# Rev_B.net
KiCad netlist of a schematic drawn in EAGLE
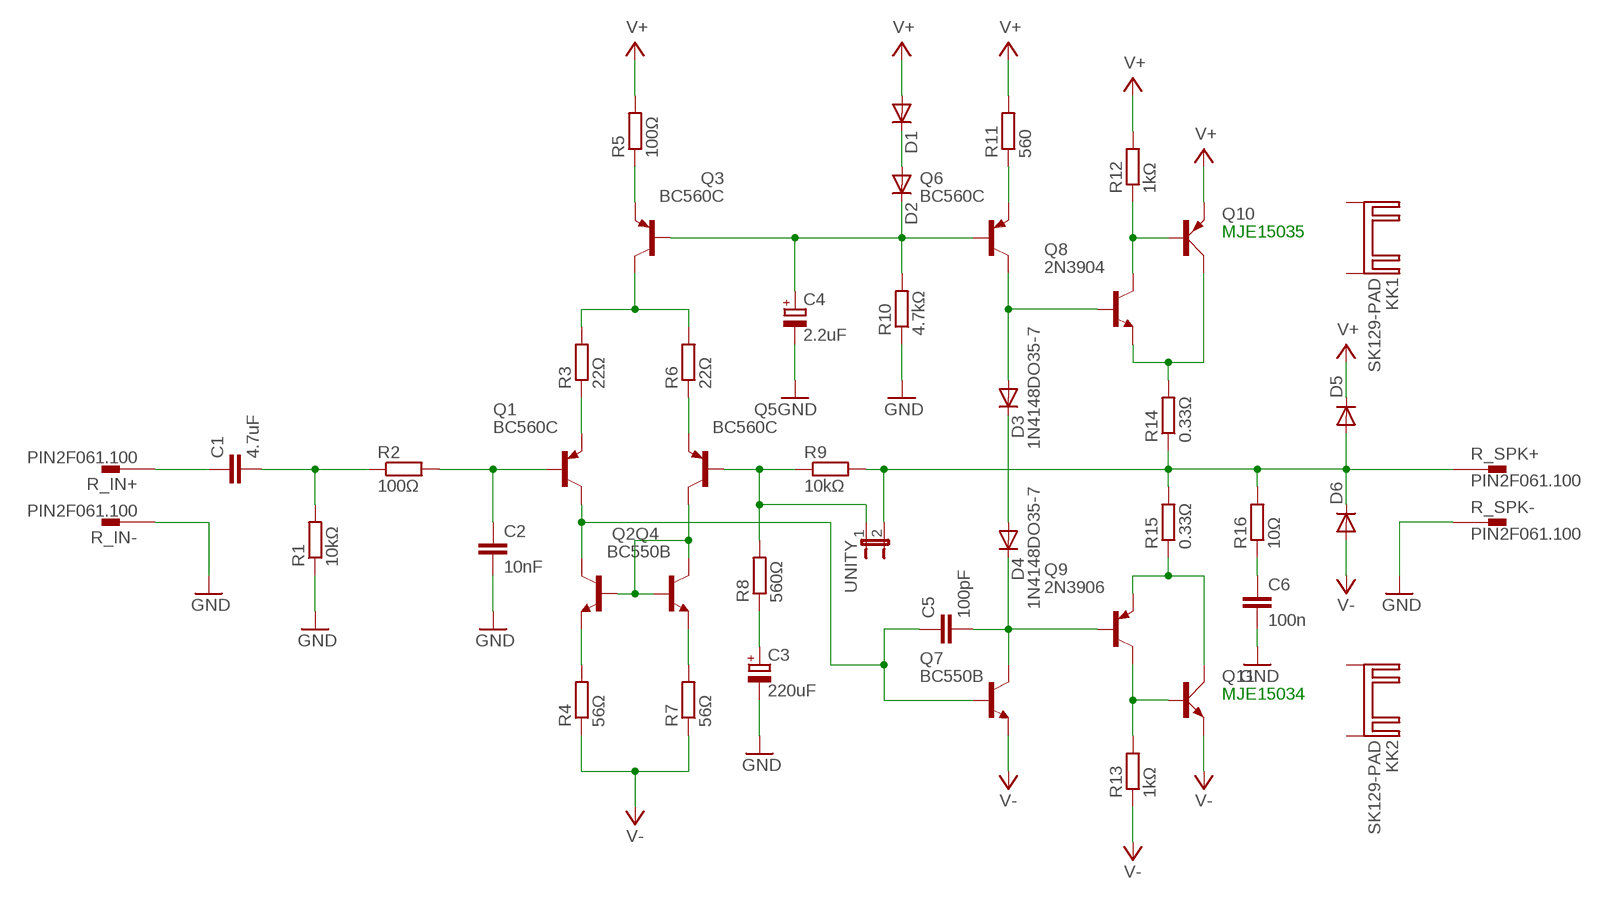
[diagram p0: schematic, sheet 1]
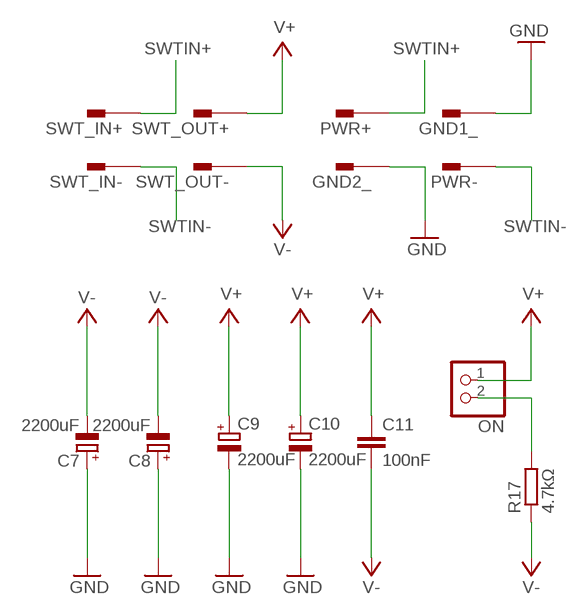
[diagram p1: schematic, sheet 2]

(export (version "E")
  (design (tool "Eeschema 10.0.6"))
  (components
    (comp (ref "C7")
      (value "2200uF")
      (footprint "eagle-import:E5-10,5")
      (libsource (lib "eagle-import") (part "CPOL-EUE5-10.5"))
    )
    (comp (ref "C8")
      (value "2200uF")
      (footprint "eagle-import:E5-10,5")
      (libsource (lib "eagle-import") (part "CPOL-EUE5-10.5"))
    )
    (comp (ref "C9")
      (value "2200uF")
      (footprint "eagle-import:E5-10,5")
      (libsource (lib "eagle-import") (part "CPOL-EUE5-10.5"))
    )
    (comp (ref "C10")
      (value "2200uF")
      (footprint "eagle-import:E5-10,5")
      (libsource (lib "eagle-import") (part "CPOL-EUE5-10.5"))
    )
    (comp (ref "C11")
      (value "100nF")
      (footprint "eagle-import:C025-025X050")
      (libsource (lib "eagle-import") (part "C-EU025-025X050"))
    )
    (comp (ref "GND1_")
      (value "PIN2F061.100")
      (footprint "eagle-import:F061.100")
      (libsource (lib "eagle-import") (part "PIN2F061.100"))
    )
    (comp (ref "GND2_")
      (value "PIN2F061.100")
      (footprint "eagle-import:F061.100")
      (libsource (lib "eagle-import") (part "PIN2F061.100"))
    )
    (comp (ref "ON")
      (value "JST_2PIN-THM")
      (footprint "eagle-import:JST-PH-2-THM")
      (libsource (lib "eagle-import") (part "JST_2PIN-THM"))
    )
    (comp (ref "PWR+")
      (value "PIN2F061.100")
      (footprint "eagle-import:F061.100")
      (libsource (lib "eagle-import") (part "PIN2F061.100"))
    )
    (comp (ref "PWR-")
      (value "PIN2F061.100")
      (footprint "eagle-import:F061.100")
      (libsource (lib "eagle-import") (part "PIN2F061.100"))
    )
    (comp (ref "R17")
      (value "4.7kΩ")
      (footprint "eagle-import:0207_10")
      (libsource (lib "eagle-import") (part "R-EU_0207/10"))
    )
    (comp (ref "SWT_IN+")
      (value "PIN2F061.100")
      (footprint "eagle-import:F061.100")
      (libsource (lib "eagle-import") (part "PIN2F061.100"))
    )
    (comp (ref "SWT_IN-")
      (value "PIN2F061.100")
      (footprint "eagle-import:F061.100")
      (libsource (lib "eagle-import") (part "PIN2F061.100"))
    )
    (comp (ref "SWT_OUT+")
      (value "PIN2F061.100")
      (footprint "eagle-import:F061.100")
      (libsource (lib "eagle-import") (part "PIN2F061.100"))
    )
    (comp (ref "SWT_OUT-")
      (value "PIN2F061.100")
      (footprint "eagle-import:F061.100")
      (libsource (lib "eagle-import") (part "PIN2F061.100"))
    )
    (comp (ref "C1")
      (value "4.7uF")
      (footprint "eagle-import:C225-113X268")
      (libsource (lib "eagle-import") (part "C-EU225-113X268"))
    )
    (comp (ref "C2")
      (value "10nF")
      (footprint "eagle-import:C025-025X050")
      (libsource (lib "eagle-import") (part "C-EU025-025X050"))
    )
    (comp (ref "C3")
      (value "220uF")
      (footprint "eagle-import:E3,5-8")
      (libsource (lib "eagle-import") (part "CPOL-EUE3.5-8"))
    )
    (comp (ref "C4")
      (value "2.2uF")
      (footprint "eagle-import:E2-5")
      (libsource (lib "eagle-import") (part "CPOL-EUE2-5"))
    )
    (comp (ref "C5")
      (value "100pF")
      (footprint "eagle-import:C050-050X075")
      (libsource (lib "eagle-import") (part "C-EU050-050X075"))
    )
    (comp (ref "C6")
      (value "100n")
      (footprint "eagle-import:C075-042X103")
      (libsource (lib "eagle-import") (part "C-EU075-042X103"))
    )
    (comp (ref "D1")
      (value "1N4148DO35-7")
      (footprint "eagle-import:DO35-7")
      (libsource (lib "eagle-import") (part "1N4148DO35-7"))
    )
    (comp (ref "D2")
      (value "1N4148DO35-7")
      (footprint "eagle-import:DO35-7")
      (libsource (lib "eagle-import") (part "1N4148DO35-7"))
    )
    (comp (ref "D3")
      (value "1N4148DO35-7")
      (footprint "eagle-import:DO35-7")
      (libsource (lib "eagle-import") (part "1N4148DO35-7"))
    )
    (comp (ref "D4")
      (value "1N4148DO35-7")
      (footprint "eagle-import:DO35-7")
      (libsource (lib "eagle-import") (part "1N4148DO35-7"))
    )
    (comp (ref "D5")
      (value "1N4148DO35-7")
      (footprint "eagle-import:DO35-7")
      (libsource (lib "eagle-import") (part "1N4148DO35-7"))
    )
    (comp (ref "D6")
      (value "1N4148DO35-7")
      (footprint "eagle-import:DO35-7")
      (libsource (lib "eagle-import") (part "1N4148DO35-7"))
    )
    (comp (ref "KK1")
      (value "SK129-PAD")
      (footprint "eagle-import:SK129")
      (libsource (lib "eagle-import") (part "SK129-PAD"))
    )
    (comp (ref "KK2")
      (value "SK129-PAD")
      (footprint "eagle-import:SK129")
      (libsource (lib "eagle-import") (part "SK129-PAD"))
    )
    (comp (ref "Q1")
      (value "BC560C")
      (footprint "eagle-import:TO92-EBC")
      (libsource (lib "eagle-import") (part "BC560C"))
    )
    (comp (ref "Q2")
      (value "BC550B")
      (footprint "eagle-import:TO92-EBC")
      (libsource (lib "eagle-import") (part "BC550B"))
    )
    (comp (ref "Q3")
      (value "BC560C")
      (footprint "eagle-import:TO92-EBC")
      (libsource (lib "eagle-import") (part "BC560C"))
    )
    (comp (ref "Q4")
      (value "BC550B")
      (footprint "eagle-import:TO92-EBC")
      (libsource (lib "eagle-import") (part "BC550B"))
    )
    (comp (ref "Q5")
      (value "BC560C")
      (footprint "eagle-import:TO92-EBC")
      (libsource (lib "eagle-import") (part "BC560C"))
    )
    (comp (ref "Q6")
      (value "BC560C")
      (footprint "eagle-import:TO92-EBC")
      (libsource (lib "eagle-import") (part "BC560C"))
    )
    (comp (ref "Q7")
      (value "BC550B")
      (footprint "eagle-import:TO92-EBC")
      (libsource (lib "eagle-import") (part "BC550B"))
    )
    (comp (ref "Q8")
      (value "2N3904")
      (footprint "eagle-import:TO92")
      (libsource (lib "eagle-import") (part "2N3904"))
    )
    (comp (ref "Q9")
      (value "2N3906")
      (footprint "eagle-import:TO92")
      (libsource (lib "eagle-import") (part "2N3906"))
    )
    (comp (ref "Q10")
      (value "TIP42C")
      (footprint "eagle-import:TO220AV")
      (libsource (lib "eagle-import") (part "TIP42C"))
    )
    (comp (ref "Q11")
      (value "TIP41C")
      (footprint "eagle-import:TO220AV")
      (libsource (lib "eagle-import") (part "TIP41C"))
    )
    (comp (ref "R1")
      (value "10kΩ")
      (footprint "eagle-import:0207_10")
      (libsource (lib "eagle-import") (part "R-EU_0207/10"))
    )
    (comp (ref "R2")
      (value "100Ω")
      (footprint "eagle-import:0207_10")
      (libsource (lib "eagle-import") (part "R-EU_0207/10"))
    )
    (comp (ref "R3")
      (value "22Ω")
      (footprint "eagle-import:0207_10")
      (libsource (lib "eagle-import") (part "R-EU_0207/10"))
    )
    (comp (ref "R4")
      (value "56Ω")
      (footprint "eagle-import:0207_10")
      (libsource (lib "eagle-import") (part "R-EU_0207/10"))
    )
    (comp (ref "R5")
      (value "100Ω")
      (footprint "eagle-import:0207_10")
      (libsource (lib "eagle-import") (part "R-EU_0207/10"))
    )
    (comp (ref "R6")
      (value "22Ω")
      (footprint "eagle-import:0207_10")
      (libsource (lib "eagle-import") (part "R-EU_0207/10"))
    )
    (comp (ref "R7")
      (value "56Ω")
      (footprint "eagle-import:0207_10")
      (libsource (lib "eagle-import") (part "R-EU_0207/10"))
    )
    (comp (ref "R8")
      (value "560Ω")
      (footprint "eagle-import:0207_10")
      (libsource (lib "eagle-import") (part "R-EU_0207/10"))
    )
    (comp (ref "R9")
      (value "10kΩ")
      (footprint "eagle-import:0207_10")
      (libsource (lib "eagle-import") (part "R-EU_0207/10"))
    )
    (comp (ref "R10")
      (value "4.7kΩ")
      (footprint "eagle-import:0207_10")
      (libsource (lib "eagle-import") (part "R-EU_0207/10"))
    )
    (comp (ref "R11")
      (value "560")
      (footprint "eagle-import:0207_10")
      (libsource (lib "eagle-import") (part "R-EU_0207/10"))
    )
    (comp (ref "R12")
      (value "1kΩ")
      (footprint "eagle-import:0207_10")
      (libsource (lib "eagle-import") (part "R-EU_0207/10"))
    )
    (comp (ref "R13")
      (value "1kΩ")
      (footprint "eagle-import:0207_10")
      (libsource (lib "eagle-import") (part "R-EU_0207/10"))
    )
    (comp (ref "R14")
      (value "0.33Ω")
      (footprint "eagle-import:0309_12")
      (libsource (lib "eagle-import") (part "R-EU_0309/12"))
    )
    (comp (ref "R15")
      (value "0.33Ω")
      (footprint "eagle-import:0309_12")
      (libsource (lib "eagle-import") (part "R-EU_0309/12"))
    )
    (comp (ref "R16")
      (value "10Ω")
      (footprint "eagle-import:0617V")
      (libsource (lib "eagle-import") (part "R-EU_0617/5V"))
    )
    (comp (ref "R_IN+")
      (value "PIN2F061.100")
      (footprint "eagle-import:F061.100")
      (libsource (lib "eagle-import") (part "PIN2F061.100"))
    )
    (comp (ref "R_IN-")
      (value "PIN2F061.100")
      (footprint "eagle-import:F061.100")
      (libsource (lib "eagle-import") (part "PIN2F061.100"))
    )
    (comp (ref "R_SPK+")
      (value "PIN2F061.100")
      (footprint "eagle-import:F061.100")
      (libsource (lib "eagle-import") (part "PIN2F061.100"))
    )
    (comp (ref "R_SPK-")
      (value "PIN2F061.100")
      (footprint "eagle-import:F061.100")
      (libsource (lib "eagle-import") (part "PIN2F061.100"))
    )
    (comp (ref "UNITY")
      (value "JP1E")
      (footprint "eagle-import:JP1")
      (libsource (lib "eagle-import") (part "JP1E"))
    )
  )
  (nets
    (net (code "1") (name "GND") (class "Default")
      (node (ref "C10") (pin "-") (pinfunction "-_-") (pintype "passive"))
      (node (ref "C2") (pin "2") (pinfunction "2_2") (pintype "passive"))
      (node (ref "C3") (pin "-") (pinfunction "-_-") (pintype "passive"))
      (node (ref "C4") (pin "-") (pinfunction "-_-") (pintype "passive"))
      (node (ref "C6") (pin "2") (pinfunction "2_2") (pintype "passive"))
      (node (ref "C7") (pin "+") (pinfunction "+_+") (pintype "passive"))
      (node (ref "C8") (pin "+") (pinfunction "+_+") (pintype "passive"))
      (node (ref "C9") (pin "-") (pinfunction "-_-") (pintype "passive"))
      (node (ref "GND1_") (pin "A1") (pinfunction "1_A1") (pintype "passive"))
      (node (ref "GND1_") (pin "A2") (pinfunction "1_A2") (pintype "passive"))
      (node (ref "GND2_") (pin "A1") (pinfunction "1_A1") (pintype "passive"))
      (node (ref "GND2_") (pin "A2") (pinfunction "1_A2") (pintype "passive"))
      (node (ref "R1") (pin "1") (pinfunction "1_1") (pintype "passive"))
      (node (ref "R10") (pin "1") (pinfunction "1_1") (pintype "passive"))
      (node (ref "R_IN-") (pin "A1") (pinfunction "1_A1") (pintype "passive"))
      (node (ref "R_IN-") (pin "A2") (pinfunction "1_A2") (pintype "passive"))
      (node (ref "R_SPK-") (pin "A1") (pinfunction "1_A1") (pintype "passive"))
      (node (ref "R_SPK-") (pin "A2") (pinfunction "1_A2") (pintype "passive"))
    )
    (net (code "2") (name "Net-(C1-Pad1)") (class "Default")
      (node (ref "C1") (pin "1") (pinfunction "1_1") (pintype "passive"))
      (node (ref "R_IN+") (pin "A1") (pinfunction "1_A1") (pintype "passive"))
      (node (ref "R_IN+") (pin "A2") (pinfunction "1_A2") (pintype "passive"))
    )
    (net (code "3") (name "Net-(C1-Pad2)") (class "Default")
      (node (ref "C1") (pin "2") (pinfunction "2_2") (pintype "passive"))
      (node (ref "R1") (pin "2") (pinfunction "2_2") (pintype "passive"))
      (node (ref "R2") (pin "1") (pinfunction "1_1") (pintype "passive"))
    )
    (net (code "4") (name "Net-(C2-Pad1)") (class "Default")
      (node (ref "C2") (pin "1") (pinfunction "1_1") (pintype "passive"))
      (node (ref "Q1") (pin "B") (pinfunction "B_B") (pintype "passive"))
      (node (ref "R2") (pin "2") (pinfunction "2_2") (pintype "passive"))
    )
    (net (code "5") (name "Net-(C3-Pad+)") (class "Default")
      (node (ref "C3") (pin "+") (pinfunction "+_+") (pintype "passive"))
      (node (ref "R8") (pin "1") (pinfunction "1_1") (pintype "passive"))
    )
    (net (code "6") (name "Net-(C4-Pad+)") (class "Default")
      (node (ref "C4") (pin "+") (pinfunction "+_+") (pintype "passive"))
      (node (ref "D2") (pin "C") (pinfunction "C_C") (pintype "passive"))
      (node (ref "Q3") (pin "B") (pinfunction "B_B") (pintype "passive"))
      (node (ref "Q6") (pin "B") (pinfunction "B_B") (pintype "passive"))
      (node (ref "R10") (pin "2") (pinfunction "2_2") (pintype "passive"))
    )
    (net (code "7") (name "Net-(C5-Pad1)") (class "Default")
      (node (ref "C5") (pin "1") (pinfunction "1_1") (pintype "passive"))
      (node (ref "Q1") (pin "C") (pinfunction "C_C") (pintype "passive"))
      (node (ref "Q2") (pin "C") (pinfunction "C_C") (pintype "passive"))
      (node (ref "Q7") (pin "B") (pinfunction "B_B") (pintype "passive"))
    )
    (net (code "8") (name "Net-(C6-Pad1)") (class "Default")
      (node (ref "C6") (pin "1") (pinfunction "1_1") (pintype "passive"))
      (node (ref "R16") (pin "1") (pinfunction "1_1") (pintype "passive"))
    )
    (net (code "9") (name "Net-(D1-PadC)") (class "Default")
      (node (ref "D1") (pin "C") (pinfunction "C_C") (pintype "passive"))
      (node (ref "D2") (pin "A") (pinfunction "A_A") (pintype "passive"))
    )
    (net (code "10") (name "Net-(D3-PadC)") (class "Default")
      (node (ref "D3") (pin "C") (pinfunction "C_C") (pintype "passive"))
      (node (ref "D4") (pin "A") (pinfunction "A_A") (pintype "passive"))
    )
    (net (code "11") (name "Net-(D5-PadA)") (class "Default")
      (node (ref "D5") (pin "A") (pinfunction "A_A") (pintype "passive"))
      (node (ref "D6") (pin "C") (pinfunction "C_C") (pintype "passive"))
      (node (ref "R14") (pin "1") (pinfunction "1_1") (pintype "passive"))
      (node (ref "R15") (pin "2") (pinfunction "2_2") (pintype "passive"))
      (node (ref "R16") (pin "2") (pinfunction "2_2") (pintype "passive"))
      (node (ref "R9") (pin "2") (pinfunction "2_2") (pintype "passive"))
      (node (ref "R_SPK+") (pin "A1") (pinfunction "1_A1") (pintype "passive"))
      (node (ref "R_SPK+") (pin "A2") (pinfunction "1_A2") (pintype "passive"))
      (node (ref "UNITY") (pin "2") (pinfunction "2_2") (pintype "passive"))
    )
    (net (code "12") (name "Net-(ON-1)") (class "Default")
      (node (ref "ON") (pin "2") (pinfunction "1_2") (pintype "passive"))
      (node (ref "R17") (pin "2") (pinfunction "2_2") (pintype "passive"))
    )
    (net (code "13") (name "Net-(Q1-PadE)") (class "Default")
      (node (ref "Q1") (pin "E") (pinfunction "E_E") (pintype "passive"))
      (node (ref "R3") (pin "1") (pinfunction "1_1") (pintype "passive"))
    )
    (net (code "14") (name "Net-(Q2-PadB)") (class "Default")
      (node (ref "Q2") (pin "B") (pinfunction "B_B") (pintype "passive"))
      (node (ref "Q4") (pin "B") (pinfunction "B_B") (pintype "passive"))
      (node (ref "Q4") (pin "C") (pinfunction "C_C") (pintype "passive"))
      (node (ref "Q5") (pin "C") (pinfunction "C_C") (pintype "passive"))
    )
    (net (code "15") (name "Net-(Q2-PadE)") (class "Default")
      (node (ref "Q2") (pin "E") (pinfunction "E_E") (pintype "passive"))
      (node (ref "R4") (pin "2") (pinfunction "2_2") (pintype "passive"))
    )
    (net (code "16") (name "Net-(Q3-PadC)") (class "Default")
      (node (ref "Q3") (pin "C") (pinfunction "C_C") (pintype "passive"))
      (node (ref "R3") (pin "2") (pinfunction "2_2") (pintype "passive"))
      (node (ref "R6") (pin "2") (pinfunction "2_2") (pintype "passive"))
    )
    (net (code "17") (name "Net-(Q3-PadE)") (class "Default")
      (node (ref "Q3") (pin "E") (pinfunction "E_E") (pintype "passive"))
      (node (ref "R5") (pin "1") (pinfunction "1_1") (pintype "passive"))
    )
    (net (code "18") (name "Net-(Q4-PadE)") (class "Default")
      (node (ref "Q4") (pin "E") (pinfunction "E_E") (pintype "passive"))
      (node (ref "R7") (pin "2") (pinfunction "2_2") (pintype "passive"))
    )
    (net (code "19") (name "Net-(Q5-PadB)") (class "Default")
      (node (ref "Q5") (pin "B") (pinfunction "B_B") (pintype "passive"))
      (node (ref "R8") (pin "2") (pinfunction "2_2") (pintype "passive"))
      (node (ref "R9") (pin "1") (pinfunction "1_1") (pintype "passive"))
      (node (ref "UNITY") (pin "1") (pinfunction "1_1") (pintype "passive"))
    )
    (net (code "20") (name "Net-(Q5-PadE)") (class "Default")
      (node (ref "Q5") (pin "E") (pinfunction "E_E") (pintype "passive"))
      (node (ref "R6") (pin "1") (pinfunction "1_1") (pintype "passive"))
    )
    (net (code "21") (name "Net-(Q6-PadE)") (class "Default")
      (node (ref "Q6") (pin "E") (pinfunction "E_E") (pintype "passive"))
      (node (ref "R11") (pin "1") (pinfunction "1_1") (pintype "passive"))
    )
    (net (code "22") (name "Net-(Q8-B)") (class "Default")
      (node (ref "D3") (pin "A") (pinfunction "A_A") (pintype "passive"))
      (node (ref "Q6") (pin "C") (pinfunction "C_C") (pintype "passive"))
      (node (ref "Q8") (pin "2") (pinfunction "B_2") (pintype "passive"))
    )
    (net (code "23") (name "Net-(Q8-C)") (class "Default")
      (node (ref "Q10") (pin "B") (pinfunction "B_B") (pintype "passive"))
      (node (ref "Q8") (pin "1") (pinfunction "C_1") (pintype "passive"))
      (node (ref "R12") (pin "1") (pinfunction "1_1") (pintype "passive"))
    )
    (net (code "24") (name "Net-(Q8-E)") (class "Default")
      (node (ref "Q10") (pin "C") (pinfunction "C_C") (pintype "passive"))
      (node (ref "Q8") (pin "3") (pinfunction "E_3") (pintype "passive"))
      (node (ref "R14") (pin "2") (pinfunction "2_2") (pintype "passive"))
    )
    (net (code "25") (name "Net-(Q9-B)") (class "Default")
      (node (ref "C5") (pin "2") (pinfunction "2_2") (pintype "passive"))
      (node (ref "D4") (pin "C") (pinfunction "C_C") (pintype "passive"))
      (node (ref "Q7") (pin "C") (pinfunction "C_C") (pintype "passive"))
      (node (ref "Q9") (pin "2") (pinfunction "B_2") (pintype "passive"))
    )
    (net (code "26") (name "Net-(Q9-C)") (class "Default")
      (node (ref "Q11") (pin "B") (pinfunction "B_B") (pintype "passive"))
      (node (ref "Q9") (pin "1") (pinfunction "C_1") (pintype "passive"))
      (node (ref "R13") (pin "2") (pinfunction "2_2") (pintype "passive"))
    )
    (net (code "27") (name "Net-(Q9-E)") (class "Default")
      (node (ref "Q11") (pin "C") (pinfunction "C_C") (pintype "passive"))
      (node (ref "Q9") (pin "3") (pinfunction "E_3") (pintype "passive"))
      (node (ref "R15") (pin "1") (pinfunction "1_1") (pintype "passive"))
    )
    (net (code "28") (name "SWTIN+") (class "Default")
      (node (ref "PWR+") (pin "A1") (pinfunction "1_A1") (pintype "passive"))
      (node (ref "PWR+") (pin "A2") (pinfunction "1_A2") (pintype "passive"))
      (node (ref "SWT_IN+") (pin "A1") (pinfunction "1_A1") (pintype "passive"))
      (node (ref "SWT_IN+") (pin "A2") (pinfunction "1_A2") (pintype "passive"))
    )
    (net (code "29") (name "SWTIN-") (class "Default")
      (node (ref "PWR-") (pin "A1") (pinfunction "1_A1") (pintype "passive"))
      (node (ref "PWR-") (pin "A2") (pinfunction "1_A2") (pintype "passive"))
      (node (ref "SWT_IN-") (pin "A1") (pinfunction "1_A1") (pintype "passive"))
      (node (ref "SWT_IN-") (pin "A2") (pinfunction "1_A2") (pintype "passive"))
    )
    (net (code "30") (name "V+") (class "Default")
      (node (ref "C10") (pin "+") (pinfunction "+_+") (pintype "passive"))
      (node (ref "C11") (pin "1") (pinfunction "1_1") (pintype "passive"))
      (node (ref "C9") (pin "+") (pinfunction "+_+") (pintype "passive"))
      (node (ref "D1") (pin "A") (pinfunction "A_A") (pintype "passive"))
      (node (ref "D5") (pin "C") (pinfunction "C_C") (pintype "passive"))
      (node (ref "ON") (pin "1") (pinfunction "2_1") (pintype "passive"))
      (node (ref "Q10") (pin "E") (pinfunction "E_E") (pintype "passive"))
      (node (ref "R11") (pin "2") (pinfunction "2_2") (pintype "passive"))
      (node (ref "R12") (pin "2") (pinfunction "2_2") (pintype "passive"))
      (node (ref "R5") (pin "2") (pinfunction "2_2") (pintype "passive"))
      (node (ref "SWT_OUT+") (pin "A1") (pinfunction "1_A1") (pintype "passive"))
      (node (ref "SWT_OUT+") (pin "A2") (pinfunction "1_A2") (pintype "passive"))
    )
    (net (code "31") (name "V-") (class "Default")
      (node (ref "C11") (pin "2") (pinfunction "2_2") (pintype "passive"))
      (node (ref "C7") (pin "-") (pinfunction "-_-") (pintype "passive"))
      (node (ref "C8") (pin "-") (pinfunction "-_-") (pintype "passive"))
      (node (ref "D6") (pin "A") (pinfunction "A_A") (pintype "passive"))
      (node (ref "Q11") (pin "E") (pinfunction "E_E") (pintype "passive"))
      (node (ref "Q7") (pin "E") (pinfunction "E_E") (pintype "passive"))
      (node (ref "R13") (pin "1") (pinfunction "1_1") (pintype "passive"))
      (node (ref "R17") (pin "1") (pinfunction "1_1") (pintype "passive"))
      (node (ref "R4") (pin "1") (pinfunction "1_1") (pintype "passive"))
      (node (ref "R7") (pin "1") (pinfunction "1_1") (pintype "passive"))
      (node (ref "SWT_OUT-") (pin "A1") (pinfunction "1_A1") (pintype "passive"))
      (node (ref "SWT_OUT-") (pin "A2") (pinfunction "1_A2") (pintype "passive"))
    )
    (net (code "32") (name "unconnected-(KK1-K-PadA2,5)") (class "Default")
      (node (ref "KK1") (pin "A2,5") (pinfunction "K_A2,5") (pintype "passive"))
    )
    (net (code "33") (name "unconnected-(KK1-K-PadB2,5)") (class "Default")
      (node (ref "KK1") (pin "B2,5") (pinfunction "K_B2,5") (pintype "passive"))
    )
    (net (code "34") (name "unconnected-(KK2-K-PadA2,5)") (class "Default")
      (node (ref "KK2") (pin "A2,5") (pinfunction "K_A2,5") (pintype "passive"))
    )
    (net (code "35") (name "unconnected-(KK2-K-PadB2,5)") (class "Default")
      (node (ref "KK2") (pin "B2,5") (pinfunction "K_B2,5") (pintype "passive"))
    )
  )
)
